# Power.net
KiCad netlist of a schematic drawn in Altium Designer
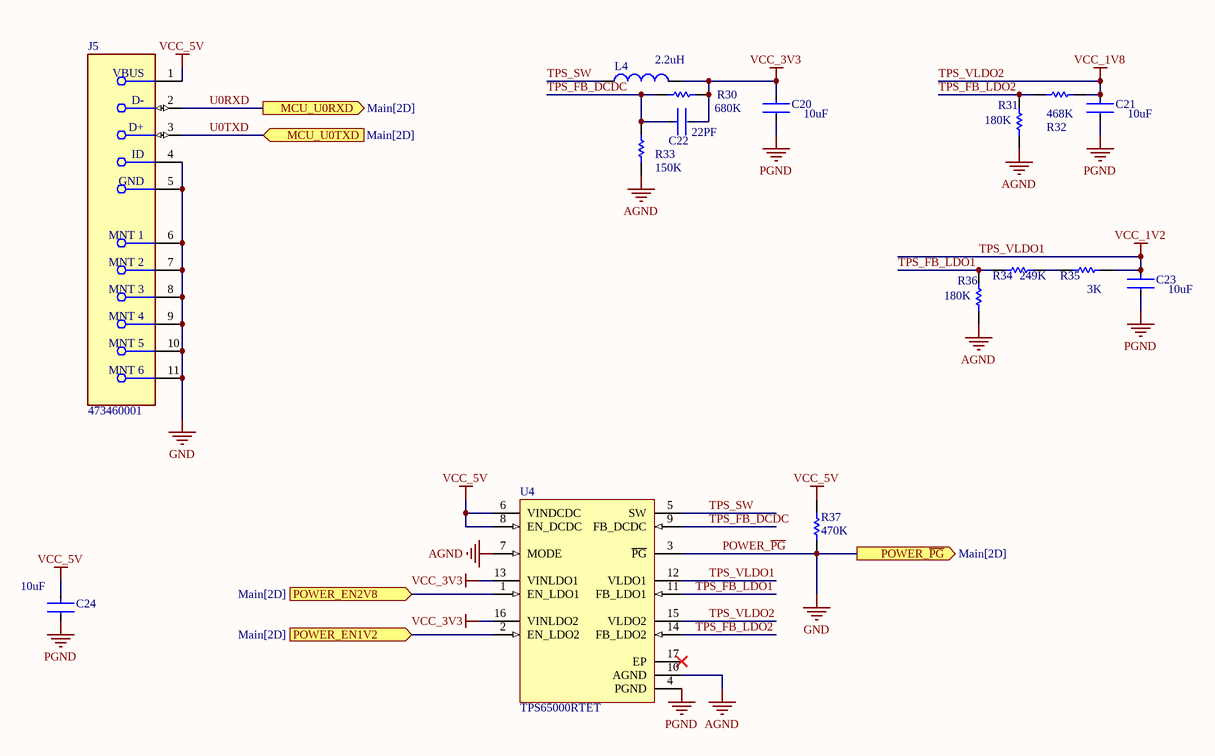
[diagram p0: Power.SchDoc]

(export (version "E")
  (design (tool "Eeschema 10.0.6"))
  (components
    (comp (ref "C20")
      (value "10uF")
      (footprint "FP-C0402C106M9PACTU-MFG")
      (description "CAP CER 10UF 6.3V X5R 0402")
      (fields (field (name "TOLERANCE") "20%"))
      (libsource (lib "Altium Content Vault") (part "b4654b650e69147ec39a6b967a45e02"))
    )
    (comp (ref "C21")
      (value "10uF")
      (footprint "FP-C0402C106M9PACTU-MFG")
      (description "CAP CER 10UF 6.3V X5R 0402")
      (fields (field (name "TOLERANCE") "20%"))
      (libsource (lib "Altium Content Vault") (part "b4654b650e69147ec39a6b967a45e02"))
    )
    (comp (ref "C22")
      (value "22PF")
      (footprint "FP-C0402C106M9PACTU-MFG")
      (description "CAP CER 10UF 6.3V X5R 0402")
      (fields (field (name "TOLERANCE") "20%"))
      (libsource (lib "Altium Content Vault") (part "b4654b650e69147ec39a6b967a45e02"))
    )
    (comp (ref "C23")
      (value "10uF")
      (footprint "FP-C0402C106M9PACTU-MFG")
      (description "CAP CER 10UF 6.3V X5R 0402")
      (fields (field (name "TOLERANCE") "20%"))
      (libsource (lib "Altium Content Vault") (part "b4654b650e69147ec39a6b967a45e02"))
    )
    (comp (ref "C24")
      (value "10uF")
      (footprint "FP-C0402C106M9PACTU-MFG")
      (description "CAP CER 10UF 6.3V X5R 0402")
      (fields (field (name "TOLERANCE") "20%"))
      (libsource (lib "Altium Content Vault") (part "b4654b650e69147ec39a6b967a45e02"))
    )
    (comp (ref "J5")
      (value "473460001")
      (footprint "FP-473460001-MFG")
      (description "CONN RCPT USB2.0 MICRO B SMD R/A")
      (fields
        (field (name "OCTOPART") "https://octopart.com/47346-0001-molex-7164928")
        (field (name "MANUFACTURER") "Molex")
      )
      (libsource (lib "Altium Content Vault") (part "53ae1f1d9b557310b43ca686e5bb76a"))
    )
    (comp (ref "L4")
      (value "2.2uH")
      (footprint "INDC2013X140X50LL20T20")
      (fields (field (name "TOLERANCE") "±20%") (field (name "MANUFACTURER") "Taiyo Yuden"))
      (libsource (lib "Altium Content Vault") (part "IND-2"))
    )
    (comp (ref "R30")
      (value "680K")
      (footprint "RESC1005X40X25LL05T05")
      (fields (field (name "MANUFACTURER") "Vishay Dale") (field (name "PART NUMBER") "CRCW040222R0FKED"))
      (libsource (lib "Altium Content Vault") (part "RES"))
    )
    (comp (ref "R31")
      (value "180K")
      (footprint "RESC1005X40X25LL05T05")
      (fields (field (name "MANUFACTURER") "Vishay Dale") (field (name "PART NUMBER") "CRCW040222R0FKED"))
      (libsource (lib "Altium Content Vault") (part "RES"))
    )
    (comp (ref "R32")
      (value "468K")
      (footprint "RESC1005X40X25LL05T05")
      (fields (field (name "MANUFACTURER") "Vishay Dale") (field (name "PART NUMBER") "CRCW040222R0FKED"))
      (libsource (lib "Altium Content Vault") (part "RES"))
    )
    (comp (ref "R33")
      (value "150K")
      (footprint "RESC1005X40X25LL05T05")
      (fields (field (name "MANUFACTURER") "Vishay Dale") (field (name "PART NUMBER") "CRCW040222R0FKED"))
      (libsource (lib "Altium Content Vault") (part "RES"))
    )
    (comp (ref "R34")
      (value "249K")
      (footprint "RESC1005X40X25LL05T05")
      (fields (field (name "MANUFACTURER") "Vishay Dale") (field (name "PART NUMBER") "CRCW040222R0FKED"))
      (libsource (lib "Altium Content Vault") (part "RES"))
    )
    (comp (ref "R35")
      (value "3K")
      (footprint "RESC1005X40X25LL05T05")
      (fields (field (name "MANUFACTURER") "Vishay Dale") (field (name "PART NUMBER") "CRCW040222R0FKED"))
      (libsource (lib "Altium Content Vault") (part "RES"))
    )
    (comp (ref "R36")
      (value "180K")
      (footprint "RESC1005X40X25LL05T05")
      (fields (field (name "MANUFACTURER") "Vishay Dale") (field (name "PART NUMBER") "CRCW040222R0FKED"))
      (libsource (lib "Altium Content Vault") (part "RES"))
    )
    (comp (ref "R37")
      (value "470K")
      (footprint "RESC1005X40X25LL05T05")
      (fields (field (name "MANUFACTURER") "Vishay Dale") (field (name "PART NUMBER") "CRCW040222R0FKED"))
      (libsource (lib "Altium Content Vault") (part "RES"))
    )
    (comp (ref "U4")
      (value "TPS65000RTET")
      (footprint "RTE0016C")
      (fields (field (name "MANUFACTURER") "Texas Instruments"))
      (libsource (lib "Altium Content Vault") (part "TI-TPS65000-RTE16"))
    )
  )
  (nets
    (net (code "1") (name "/POWER_EN1V2") (class "Default")
      (node (ref "U4") (pin "2") (pinfunction "EN_LDO2_2") (pintype "input"))
    )
    (net (code "2") (name "/POWER_EN2V8") (class "Default")
      (node (ref "U4") (pin "1") (pinfunction "EN_LDO1_1") (pintype "input"))
    )
    (net (code "3") (name "/TPS_FB_DCDC") (class "Default")
      (node (ref "C22") (pin "1") (pinfunction "1_1") (pintype "passive"))
      (node (ref "R30") (pin "2") (pinfunction "2_2") (pintype "passive"))
      (node (ref "R33") (pin "2") (pinfunction "2_2") (pintype "passive"))
      (node (ref "U4") (pin "9") (pinfunction "FB_DCDC_9") (pintype "input"))
    )
    (net (code "4") (name "/TPS_FB_LDO1") (class "Default")
      (node (ref "R34") (pin "2") (pinfunction "2_2") (pintype "passive"))
      (node (ref "R36") (pin "2") (pinfunction "2_2") (pintype "passive"))
      (node (ref "U4") (pin "11") (pinfunction "FB_LDO1_11") (pintype "input"))
    )
    (net (code "5") (name "/TPS_FB_LDO2") (class "Default")
      (node (ref "R31") (pin "2") (pinfunction "2_2") (pintype "passive"))
      (node (ref "R32") (pin "2") (pinfunction "2_2") (pintype "passive"))
      (node (ref "U4") (pin "14") (pinfunction "FB_LDO2_14") (pintype "input"))
    )
    (net (code "6") (name "/TPS_SW") (class "Default")
      (node (ref "L4") (pin "1") (pinfunction "1_1") (pintype "passive"))
      (node (ref "U4") (pin "5") (pinfunction "SW_5") (pintype "power_in"))
    )
    (net (code "7") (name "/U0RXD") (class "Default")
      (node (ref "J5") (pin "2") (pinfunction "D-_2") (pintype "bidirectional"))
    )
    (net (code "8") (name "/U0TXD") (class "Default")
      (node (ref "J5") (pin "3") (pinfunction "D+_3") (pintype "bidirectional"))
    )
    (net (code "9") (name "AGND") (class "Default")
      (node (ref "R31") (pin "1") (pinfunction "1_1") (pintype "passive"))
      (node (ref "R33") (pin "1") (pinfunction "1_1") (pintype "passive"))
      (node (ref "R36") (pin "1") (pinfunction "1_1") (pintype "passive"))
      (node (ref "U4") (pin "10") (pinfunction "AGND_10") (pintype "power_in"))
      (node (ref "U4") (pin "7") (pinfunction "MODE_7") (pintype "input"))
    )
    (net (code "10") (name "GND") (class "Default")
      (node (ref "J5") (pin "10") (pinfunction "MNT_5_10") (pintype "passive"))
      (node (ref "J5") (pin "11") (pinfunction "MNT_6_11") (pintype "passive"))
      (node (ref "J5") (pin "4") (pinfunction "ID_4") (pintype "passive"))
      (node (ref "J5") (pin "5") (pinfunction "GND_5") (pintype "power_in"))
      (node (ref "J5") (pin "6") (pinfunction "MNT_1_6") (pintype "passive"))
      (node (ref "J5") (pin "7") (pinfunction "MNT_2_7") (pintype "passive"))
      (node (ref "J5") (pin "8") (pinfunction "MNT_3_8") (pintype "passive"))
      (node (ref "J5") (pin "9") (pinfunction "MNT_4_9") (pintype "passive"))
      (node (ref "R37") (pin "2") (pinfunction "2_2") (pintype "passive"))
      (node (ref "U4") (pin "3") (pinfunction "~{PG}_3") (pintype "tri_state"))
    )
    (net (code "11") (name "Net-(R34-Pad1)") (class "Default")
      (node (ref "R34") (pin "1") (pinfunction "1_1") (pintype "passive"))
      (node (ref "R35") (pin "2") (pinfunction "2_2") (pintype "passive"))
    )
    (net (code "12") (name "PGND") (class "Default")
      (node (ref "C20") (pin "2") (pinfunction "2_2") (pintype "passive"))
      (node (ref "C21") (pin "2") (pinfunction "2_2") (pintype "passive"))
      (node (ref "C23") (pin "2") (pinfunction "2_2") (pintype "passive"))
      (node (ref "C24") (pin "2") (pinfunction "2_2") (pintype "passive"))
      (node (ref "U4") (pin "4") (pinfunction "PGND_4") (pintype "power_in"))
    )
    (net (code "13") (name "VCC_1V2") (class "Default")
      (node (ref "C23") (pin "1") (pinfunction "1_1") (pintype "passive"))
      (node (ref "R35") (pin "1") (pinfunction "1_1") (pintype "passive"))
      (node (ref "U4") (pin "12") (pinfunction "VLDO1_12") (pintype "power_in"))
    )
    (net (code "14") (name "VCC_1V8") (class "Default")
      (node (ref "C21") (pin "1") (pinfunction "1_1") (pintype "passive"))
      (node (ref "R32") (pin "1") (pinfunction "1_1") (pintype "passive"))
      (node (ref "U4") (pin "15") (pinfunction "VLDO2_15") (pintype "power_in"))
    )
    (net (code "15") (name "VCC_3V3") (class "Default")
      (node (ref "C20") (pin "1") (pinfunction "1_1") (pintype "passive"))
      (node (ref "C22") (pin "2") (pinfunction "2_2") (pintype "passive"))
      (node (ref "L4") (pin "2") (pinfunction "2_2") (pintype "passive"))
      (node (ref "R30") (pin "1") (pinfunction "1_1") (pintype "passive"))
      (node (ref "U4") (pin "13") (pinfunction "VINLDO1_13") (pintype "power_in"))
      (node (ref "U4") (pin "16") (pinfunction "VINLDO2_16") (pintype "power_in"))
    )
    (net (code "16") (name "VCC_5V") (class "Default")
      (node (ref "C24") (pin "1") (pinfunction "1_1") (pintype "passive"))
      (node (ref "J5") (pin "1") (pinfunction "VBUS_1") (pintype "power_in"))
      (node (ref "R37") (pin "1") (pinfunction "1_1") (pintype "passive"))
      (node (ref "U4") (pin "6") (pinfunction "VINDCDC_6") (pintype "power_in"))
      (node (ref "U4") (pin "8") (pinfunction "EN_DCDC_8") (pintype "input"))
    )
    (net (code "17") (name "unconnected-(U4-EP-Pad17)") (class "Default")
      (node (ref "U4") (pin "17") (pinfunction "EP_17") (pintype "power_in+no_connect"))
    )
  )
)
